# 1_Supply.net
KiCad netlist of a schematic drawn in Altium Designer
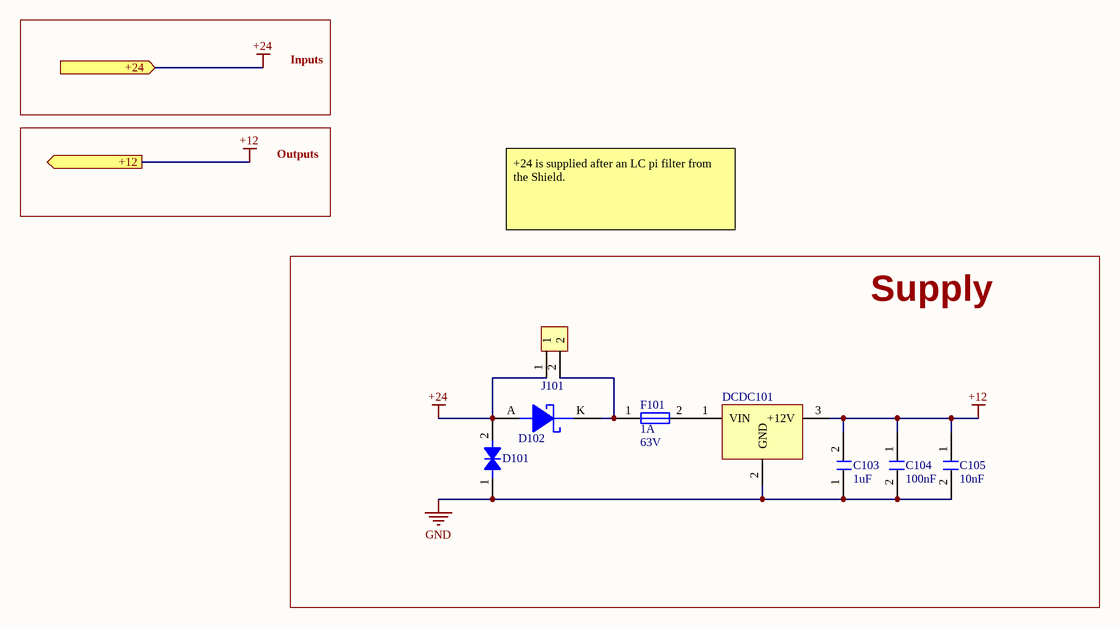
[diagram p0: [1] Supply.SchDoc]

(export (version "E")
  (design (tool "Eeschema 10.0.6"))
  (components
    (comp (ref "C103")
      (value "885012207103")
      (footprint "C0805FNPC-R")
      (fields
        (field (name "TOLERANCE") "10%")
        (field (name "CAPACITANCE") "1uF")
        (field (name ".CREATOR") "GP")
      )
      (libsource (lib "Passives") (part "C1u-50V-0805FNPC-X7R"))
    )
    (comp (ref "C104")
      (value "885012207098")
      (footprint "C0805FNPC-R")
      (description "Cap, 0.1ΜF, 50V, 10%, X7R, 0805")
      (fields
        (field (name "TOLERANCE") "10%")
        (field (name "CAPACITANCE") "100nF")
        (field (name ".CREATOR") "DR")
      )
      (libsource (lib "Passives") (part "C100n-50V-0805FNPC-X7R"))
    )
    (comp (ref "C105")
      (value "885012207092")
      (footprint "C0805FNPC-R")
      (description "Cap, 0.01ΜF, 50V, 10%, X7R, 0805")
      (fields
        (field (name "TOLERANCE") "10%")
        (field (name "CAPACITANCE") "10nF")
        (field (name ".CREATOR") "DR")
      )
      (libsource (lib "Passives") (part "C10n-50V-0805FNPC-X7R"))
    )
    (comp (ref "D101")
      (value "824551301")
      (footprint "DTVS-DO-214AB")
      (description "TVS diode [Würth Elektronik] 824551301 TVS diode")
      (fields (field (name "MANUFACTURER") "Wurth Electronics") (field (name ".CREATOR") "DO"))
      (libsource (lib "Filter components") (part "DTVS-40V-DO-214AB"))
    )
    (comp (ref "D102")
      (value "MBR0530")
      (footprint "DSC-SOD123")
      (description "VR=30V IF=500mA 30pF P=410mW")
      (fields (field (name ".CREATOR") "GP"))
      (libsource (lib "Filter components") (part "DSC-0.5/30-SOD123"))
    )
    (comp (ref "DCDC101")
      (value "173951236")
      (footprint "DCDC_Magi3c")
      (description "Fdsm Fixed Step Down Regulator M")
      (libsource (lib "Semiconductor") (part "DCDC-36V/12V-0.5A"))
    )
    (comp (ref "F101")
      (value "0437001.WRA")
      (footprint "Fuse_1206")
      (description "Fuse Chip Fast Acting 1A 63V SMD Solder Pad 1206 Ceramic T/R Automotive")
      (fields
        (field (name "MANUFACTURER") "Littelfuse")
        (field (name "CURRENT RATING") "1A")
        (field (name "VOLTAGE RATING (DC)") "63V")
        (field (name ".CREATOR") "DO")
      )
      (libsource (lib "Filter components") (part "Fuse_1A_63V_1206"))
    )
    (comp (ref "J101")
      (value "61300211121")
      (footprint "J_Pinheader_1x2")
      (description "CONN HEADER 2 POS 2.54")
      (fields (field (name "MANUFACTURER") "Molex") (field (name ".CREATOR") "GP"))
      (libsource (lib "Electromechanical") (part "J_Jumper"))
    )
  )
  (nets
    (net (code "1") (name "+12") (class "Default")
      (node (ref "C103") (pin "2") (pinfunction "2_2") (pintype "passive"))
      (node (ref "C104") (pin "1") (pinfunction "1_1") (pintype "passive"))
      (node (ref "C105") (pin "1") (pinfunction "1_1") (pintype "passive"))
      (node (ref "DCDC101") (pin "3") (pinfunction "+12V_3") (pintype "passive"))
    )
    (net (code "2") (name "+24") (class "Default")
      (node (ref "D101") (pin "2") (pinfunction "2_2") (pintype "passive"))
      (node (ref "D102") (pin "A") (pinfunction "A_A") (pintype "passive"))
      (node (ref "J101") (pin "1") (pinfunction "1_1") (pintype "passive"))
    )
    (net (code "3") (name "GND") (class "Default")
      (node (ref "C103") (pin "1") (pinfunction "1_1") (pintype "passive"))
      (node (ref "C104") (pin "2") (pinfunction "2_2") (pintype "passive"))
      (node (ref "C105") (pin "2") (pinfunction "2_2") (pintype "passive"))
      (node (ref "D101") (pin "1") (pinfunction "1_1") (pintype "passive"))
      (node (ref "DCDC101") (pin "2") (pinfunction "GND_2") (pintype "passive"))
    )
    (net (code "4") (name "Net-(D102-PadK)") (class "Default")
      (node (ref "D102") (pin "K") (pinfunction "K_K") (pintype "passive"))
      (node (ref "F101") (pin "1") (pinfunction "1_1") (pintype "passive"))
      (node (ref "J101") (pin "2") (pinfunction "2_2") (pintype "passive"))
    )
    (net (code "5") (name "Net-(DCDC101-VIN)") (class "Default")
      (node (ref "DCDC101") (pin "1") (pinfunction "VIN_1") (pintype "passive"))
      (node (ref "F101") (pin "2") (pinfunction "2_2") (pintype "passive"))
    )
  )
)
